# EXT-PHY.net
KiCad netlist of a schematic drawn in EAGLE
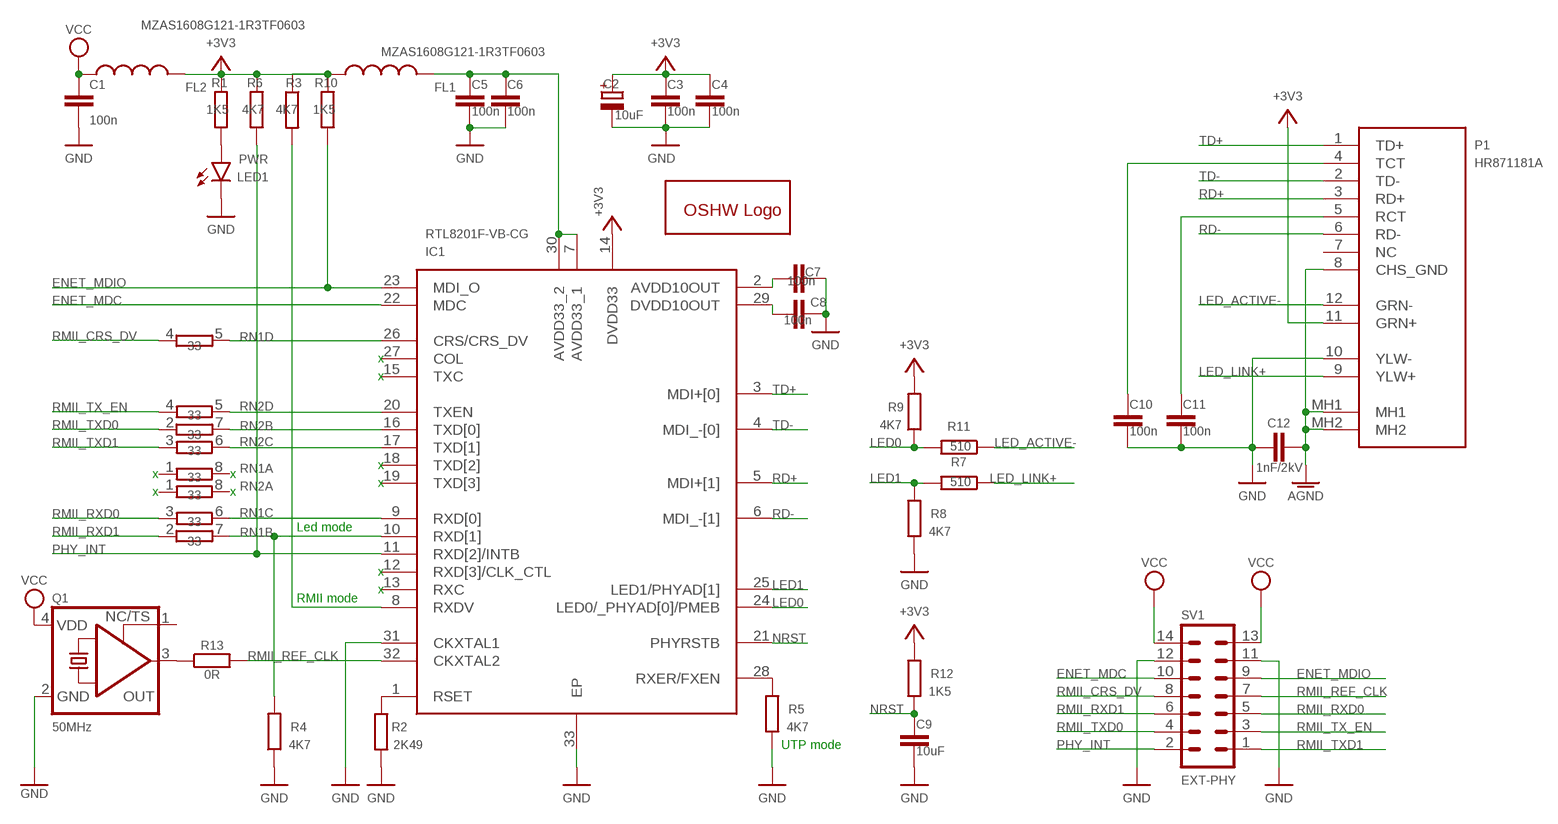
[diagram p0: schematic, sheet 1]

(export (version "E")
  (design (tool "Eeschema 10.0.6"))
  (components
    (comp (ref "C1")
      (value "100n")
      (footprint "eagle-import:C0603")
      (libsource (lib "eagle-import") (part "C-EUC0603"))
    )
    (comp (ref "C2")
      (value "10uF")
      (footprint "eagle-import:A_3216-18R")
      (libsource (lib "eagle-import") (part "CPOL-EUA/3216-18R"))
    )
    (comp (ref "C3")
      (value "100n")
      (footprint "eagle-import:C0603")
      (libsource (lib "eagle-import") (part "C-EUC0603"))
    )
    (comp (ref "C4")
      (value "100n")
      (footprint "eagle-import:C0603")
      (libsource (lib "eagle-import") (part "C-EUC0603"))
    )
    (comp (ref "C5")
      (value "100n")
      (footprint "eagle-import:C0603")
      (libsource (lib "eagle-import") (part "C-EUC0603"))
    )
    (comp (ref "C6")
      (value "100n")
      (footprint "eagle-import:C0603")
      (libsource (lib "eagle-import") (part "C-EUC0603"))
    )
    (comp (ref "C7")
      (value "100n")
      (footprint "eagle-import:C0603")
      (libsource (lib "eagle-import") (part "C-EUC0603"))
    )
    (comp (ref "C8")
      (value "100n")
      (footprint "eagle-import:C0603")
      (libsource (lib "eagle-import") (part "C-EUC0603"))
    )
    (comp (ref "C9")
      (value "10uF")
      (footprint "eagle-import:C0603")
      (libsource (lib "eagle-import") (part "C-EUC0603"))
    )
    (comp (ref "C10")
      (value "100n")
      (footprint "eagle-import:C0603")
      (libsource (lib "eagle-import") (part "C-EUC0603"))
    )
    (comp (ref "C11")
      (value "100n")
      (footprint "eagle-import:C0603")
      (libsource (lib "eagle-import") (part "C-EUC0603"))
    )
    (comp (ref "C12")
      (value "1nF/2kV")
      (footprint "eagle-import:C1206")
      (fields (field (name "SPICEPREFIX") "C"))
      (libsource (lib "eagle-import") (part "C-EUC1206"))
    )
    (comp (ref "FL1")
      (value "MZAS1608G121-1R3TF0603")
      (footprint "eagle-import:0603")
      (libsource (lib "eagle-import") (part "MZAS1608G121-1R3TF0603"))
    )
    (comp (ref "FL2")
      (value "MZAS1608G121-1R3TF0603")
      (footprint "eagle-import:0603")
      (libsource (lib "eagle-import") (part "MZAS1608G121-1R3TF0603"))
    )
    (comp (ref "GOLD_ORB_SM1")
      (value "OSHWLOGOLOGO5MM")
      (footprint "eagle-import:OSHW_5MM")
      (libsource (lib "eagle-import") (part "OSHWLOGOLOGO5MM"))
    )
    (comp (ref "IC1")
      (value "RTL8201F-VB-CG")
      (footprint "eagle-import:QFN50P500X500X100-33N")
      (libsource (lib "eagle-import") (part "RTL8201F-VB-CG"))
    )
    (comp (ref "LED1")
      (value "PWR")
      (footprint "eagle-import:CHIP-LED0603")
      (libsource (lib "eagle-import") (part "LEDCHIP-LED0603"))
    )
    (comp (ref "P1")
      (value "HR871181A")
      (footprint "eagle-import:HR871181A")
      (libsource (lib "eagle-import") (part "HR871181A"))
    )
    (comp (ref "Q1")
      (value "50MHz")
      (footprint "eagle-import:3.2X2.5_KXO-V96")
      (libsource (lib "eagle-import") (part "KXO-PXO/XO-V96"))
    )
    (comp (ref "R1")
      (value "1K5")
      (footprint "eagle-import:R0603")
      (libsource (lib "eagle-import") (part "R-EU_R0603"))
    )
    (comp (ref "R2")
      (value "2K49")
      (footprint "eagle-import:R0603")
      (libsource (lib "eagle-import") (part "R-EU_R0603"))
    )
    (comp (ref "R3")
      (value "4K7")
      (footprint "eagle-import:R0603")
      (libsource (lib "eagle-import") (part "R-EU_R0603"))
    )
    (comp (ref "R4")
      (value "4K7")
      (footprint "eagle-import:R0603")
      (libsource (lib "eagle-import") (part "R-EU_R0603"))
    )
    (comp (ref "R5")
      (value "4K7")
      (footprint "eagle-import:R0603")
      (libsource (lib "eagle-import") (part "R-EU_R0603"))
    )
    (comp (ref "R6")
      (value "4K7")
      (footprint "eagle-import:R0603")
      (libsource (lib "eagle-import") (part "R-EU_R0603"))
    )
    (comp (ref "R7")
      (value "510")
      (footprint "eagle-import:R0603")
      (libsource (lib "eagle-import") (part "R-EU_R0603"))
    )
    (comp (ref "R8")
      (value "4K7")
      (footprint "eagle-import:R0603")
      (libsource (lib "eagle-import") (part "R-EU_R0603"))
    )
    (comp (ref "R9")
      (value "4K7")
      (footprint "eagle-import:R0603")
      (libsource (lib "eagle-import") (part "R-EU_R0603"))
    )
    (comp (ref "R10")
      (value "1K5")
      (footprint "eagle-import:R0603")
      (libsource (lib "eagle-import") (part "R-EU_R0603"))
    )
    (comp (ref "R11")
      (value "510")
      (footprint "eagle-import:R0603")
      (libsource (lib "eagle-import") (part "R-EU_R0603"))
    )
    (comp (ref "R12")
      (value "1K5")
      (footprint "eagle-import:R0603")
      (libsource (lib "eagle-import") (part "R-EU_R0603"))
    )
    (comp (ref "R13")
      (value "0R")
      (footprint "eagle-import:R0603")
      (libsource (lib "eagle-import") (part "R-EU_R0603"))
    )
    (comp (ref "RN1")
      (value "33")
      (footprint "eagle-import:4X0402ARV341")
      (fields (field (name "JLCPCB") "C25501"))
      (libsource (lib "eagle-import") (part "4R-N0402ARV341"))
    )
    (comp (ref "RN2")
      (value "33")
      (footprint "eagle-import:4X0402ARV341")
      (fields (field (name "JLCPCB") "C25501"))
      (libsource (lib "eagle-import") (part "4R-N0402ARV341"))
    )
    (comp (ref "SV1")
      (value "EXT-PHY")
      (footprint "eagle-import:MA07-2W")
      (libsource (lib "eagle-import") (part "MA07-2W"))
    )
  )
  (nets
    (net (code "1") (name "+3V3") (class "Default")
      (node (ref "C2") (pin "+") (pinfunction "+_+") (pintype "passive"))
      (node (ref "C3") (pin "1") (pinfunction "1_1") (pintype "passive"))
      (node (ref "C4") (pin "1") (pinfunction "1_1") (pintype "passive"))
      (node (ref "FL1") (pin "1") (pinfunction "1_1") (pintype "passive"))
      (node (ref "FL2") (pin "2") (pinfunction "2_2") (pintype "passive"))
      (node (ref "IC1") (pin "14") (pinfunction "DVDD33_14") (pintype "bidirectional"))
      (node (ref "P1") (pin "11") (pinfunction "GRN+_11") (pintype "bidirectional"))
      (node (ref "R1") (pin "2") (pinfunction "2_2") (pintype "passive"))
      (node (ref "R10") (pin "2") (pinfunction "2_2") (pintype "passive"))
      (node (ref "R12") (pin "2") (pinfunction "2_2") (pintype "passive"))
      (node (ref "R3") (pin "1") (pinfunction "1_1") (pintype "passive"))
      (node (ref "R6") (pin "2") (pinfunction "2_2") (pintype "passive"))
      (node (ref "R9") (pin "2") (pinfunction "2_2") (pintype "passive"))
    )
    (net (code "2") (name "/ENET_MDC") (class "Default")
      (node (ref "IC1") (pin "22") (pinfunction "MDC_22") (pintype "bidirectional"))
      (node (ref "SV1") (pin "10") (pinfunction "10_10") (pintype "passive"))
    )
    (net (code "3") (name "/ENET_MDIO") (class "Default")
      (node (ref "IC1") (pin "23") (pinfunction "MDI_O_23") (pintype "bidirectional"))
      (node (ref "R10") (pin "1") (pinfunction "1_1") (pintype "passive"))
      (node (ref "SV1") (pin "9") (pinfunction "9_9") (pintype "passive"))
    )
    (net (code "4") (name "/LED0") (class "Default")
      (node (ref "IC1") (pin "24") (pinfunction "LED0/_PHYAD[0]/PMEB_24") (pintype "bidirectional"))
      (node (ref "R11") (pin "2") (pinfunction "2_2") (pintype "passive"))
      (node (ref "R9") (pin "1") (pinfunction "1_1") (pintype "passive"))
    )
    (net (code "5") (name "/LED1") (class "Default")
      (node (ref "IC1") (pin "25") (pinfunction "LED1/PHYAD[1]_25") (pintype "bidirectional"))
      (node (ref "R7") (pin "2") (pinfunction "2_2") (pintype "passive"))
      (node (ref "R8") (pin "2") (pinfunction "2_2") (pintype "passive"))
    )
    (net (code "6") (name "/LED_ACTIVE-") (class "Default")
      (node (ref "P1") (pin "12") (pinfunction "GRN-_12") (pintype "bidirectional"))
      (node (ref "R11") (pin "1") (pinfunction "1_1") (pintype "passive"))
    )
    (net (code "7") (name "/LED_LINK+") (class "Default")
      (node (ref "P1") (pin "9") (pinfunction "YLW+_9") (pintype "bidirectional"))
      (node (ref "R7") (pin "1") (pinfunction "1_1") (pintype "passive"))
    )
    (net (code "8") (name "/NRST") (class "Default")
      (node (ref "C9") (pin "1") (pinfunction "1_1") (pintype "passive"))
      (node (ref "IC1") (pin "21") (pinfunction "PHYRSTB_21") (pintype "bidirectional"))
      (node (ref "R12") (pin "1") (pinfunction "1_1") (pintype "passive"))
    )
    (net (code "9") (name "/PHY_INT") (class "Default")
      (node (ref "IC1") (pin "11") (pinfunction "RXD[2]/INTB_11") (pintype "bidirectional"))
      (node (ref "R6") (pin "1") (pinfunction "1_1") (pintype "passive"))
      (node (ref "SV1") (pin "2") (pinfunction "2_2") (pintype "passive"))
    )
    (net (code "10") (name "/RD+") (class "Default")
      (node (ref "IC1") (pin "5") (pinfunction "MDI+[1]_5") (pintype "bidirectional"))
      (node (ref "P1") (pin "3") (pinfunction "RD+_3") (pintype "bidirectional"))
    )
    (net (code "11") (name "/RD-") (class "Default")
      (node (ref "IC1") (pin "6") (pinfunction "MDI_-[1]_6") (pintype "bidirectional"))
      (node (ref "P1") (pin "6") (pinfunction "RD-_6") (pintype "bidirectional"))
    )
    (net (code "12") (name "/RMII_CRS_DV") (class "Default")
      (node (ref "RN1") (pin "4") (pinfunction "1_4") (pintype "passive"))
      (node (ref "SV1") (pin "8") (pinfunction "8_8") (pintype "passive"))
    )
    (net (code "13") (name "/RMII_REF_CLK") (class "Default")
      (node (ref "IC1") (pin "32") (pinfunction "CKXTAL2_32") (pintype "bidirectional"))
      (node (ref "R13") (pin "2") (pinfunction "2_2") (pintype "passive"))
      (node (ref "SV1") (pin "7") (pinfunction "7_7") (pintype "passive"))
    )
    (net (code "14") (name "/RMII_RXD0") (class "Default")
      (node (ref "RN1") (pin "3") (pinfunction "1_3") (pintype "passive"))
      (node (ref "SV1") (pin "5") (pinfunction "5_5") (pintype "passive"))
    )
    (net (code "15") (name "/RMII_RXD1") (class "Default")
      (node (ref "RN1") (pin "2") (pinfunction "1_2") (pintype "passive"))
      (node (ref "SV1") (pin "6") (pinfunction "6_6") (pintype "passive"))
    )
    (net (code "16") (name "/RMII_TXD0") (class "Default")
      (node (ref "RN2") (pin "2") (pinfunction "1_2") (pintype "passive"))
      (node (ref "SV1") (pin "4") (pinfunction "4_4") (pintype "passive"))
    )
    (net (code "17") (name "/RMII_TXD1") (class "Default")
      (node (ref "RN2") (pin "3") (pinfunction "1_3") (pintype "passive"))
      (node (ref "SV1") (pin "1") (pinfunction "1_1") (pintype "passive"))
    )
    (net (code "18") (name "/RMII_TX_EN") (class "Default")
      (node (ref "RN2") (pin "4") (pinfunction "1_4") (pintype "passive"))
      (node (ref "SV1") (pin "3") (pinfunction "3_3") (pintype "passive"))
    )
    (net (code "19") (name "/TD+") (class "Default")
      (node (ref "IC1") (pin "3") (pinfunction "MDI+[0]_3") (pintype "bidirectional"))
      (node (ref "P1") (pin "1") (pinfunction "TD+_1") (pintype "bidirectional"))
    )
    (net (code "20") (name "/TD-") (class "Default")
      (node (ref "IC1") (pin "4") (pinfunction "MDI_-[0]_4") (pintype "bidirectional"))
      (node (ref "P1") (pin "2") (pinfunction "TD-_2") (pintype "bidirectional"))
    )
    (net (code "21") (name "AGND") (class "Default")
      (node (ref "C12") (pin "2") (pinfunction "2_2") (pintype "passive"))
      (node (ref "P1") (pin "8") (pinfunction "CHS_GND_8") (pintype "bidirectional"))
      (node (ref "P1") (pin "MH1") (pinfunction "MH1_MH1") (pintype "bidirectional"))
      (node (ref "P1") (pin "MH2") (pinfunction "MH2_MH2") (pintype "bidirectional"))
    )
    (net (code "22") (name "GND") (class "Default")
      (node (ref "C1") (pin "2") (pinfunction "2_2") (pintype "passive"))
      (node (ref "C10") (pin "2") (pinfunction "2_2") (pintype "passive"))
      (node (ref "C11") (pin "2") (pinfunction "2_2") (pintype "passive"))
      (node (ref "C12") (pin "1") (pinfunction "1_1") (pintype "passive"))
      (node (ref "C2") (pin "-") (pinfunction "-_-") (pintype "passive"))
      (node (ref "C3") (pin "2") (pinfunction "2_2") (pintype "passive"))
      (node (ref "C4") (pin "2") (pinfunction "2_2") (pintype "passive"))
      (node (ref "C5") (pin "2") (pinfunction "2_2") (pintype "passive"))
      (node (ref "C6") (pin "2") (pinfunction "2_2") (pintype "passive"))
      (node (ref "C7") (pin "2") (pinfunction "2_2") (pintype "passive"))
      (node (ref "C8") (pin "1") (pinfunction "1_1") (pintype "passive"))
      (node (ref "C9") (pin "2") (pinfunction "2_2") (pintype "passive"))
      (node (ref "IC1") (pin "31") (pinfunction "CKXTAL1_31") (pintype "bidirectional"))
      (node (ref "IC1") (pin "33") (pinfunction "EP_33") (pintype "bidirectional"))
      (node (ref "LED1") (pin "C") (pinfunction "C_C") (pintype "passive"))
      (node (ref "P1") (pin "10") (pinfunction "YLW-_10") (pintype "bidirectional"))
      (node (ref "Q1") (pin "2") (pinfunction "GND_2") (pintype "power_in"))
      (node (ref "R2") (pin "2") (pinfunction "2_2") (pintype "passive"))
      (node (ref "R4") (pin "1") (pinfunction "1_1") (pintype "passive"))
      (node (ref "R5") (pin "1") (pinfunction "1_1") (pintype "passive"))
      (node (ref "R8") (pin "1") (pinfunction "1_1") (pintype "passive"))
      (node (ref "SV1") (pin "11") (pinfunction "11_11") (pintype "passive"))
      (node (ref "SV1") (pin "12") (pinfunction "12_12") (pintype "passive"))
    )
    (net (code "23") (name "Net-(IC1-AVDD10OUT)") (class "Default")
      (node (ref "C7") (pin "1") (pinfunction "1_1") (pintype "passive"))
      (node (ref "IC1") (pin "2") (pinfunction "AVDD10OUT_2") (pintype "bidirectional"))
    )
    (net (code "24") (name "Net-(IC1-AVDD33_1)") (class "Default")
      (node (ref "C5") (pin "1") (pinfunction "1_1") (pintype "passive"))
      (node (ref "C6") (pin "1") (pinfunction "1_1") (pintype "passive"))
      (node (ref "FL1") (pin "2") (pinfunction "2_2") (pintype "passive"))
      (node (ref "IC1") (pin "30") (pinfunction "AVDD33_2_30") (pintype "bidirectional"))
      (node (ref "IC1") (pin "7") (pinfunction "AVDD33_1_7") (pintype "bidirectional"))
    )
    (net (code "25") (name "Net-(IC1-CRS{slash}CRS_DV)") (class "Default")
      (node (ref "IC1") (pin "26") (pinfunction "CRS/CRS_DV_26") (pintype "bidirectional"))
      (node (ref "RN1") (pin "5") (pinfunction "2_5") (pintype "passive"))
    )
    (net (code "26") (name "Net-(IC1-DVDD10OUT)") (class "Default")
      (node (ref "C8") (pin "2") (pinfunction "2_2") (pintype "passive"))
      (node (ref "IC1") (pin "29") (pinfunction "DVDD10OUT_29") (pintype "bidirectional"))
    )
    (net (code "27") (name "Net-(IC1-RSET)") (class "Default")
      (node (ref "IC1") (pin "1") (pinfunction "RSET_1") (pintype "bidirectional"))
      (node (ref "R2") (pin "1") (pinfunction "1_1") (pintype "passive"))
    )
    (net (code "28") (name "Net-(IC1-RXDV)") (class "Default")
      (node (ref "IC1") (pin "8") (pinfunction "RXDV_8") (pintype "bidirectional"))
      (node (ref "R3") (pin "2") (pinfunction "2_2") (pintype "passive"))
    )
    (net (code "29") (name "Net-(IC1-RXD[0])") (class "Default")
      (node (ref "IC1") (pin "9") (pinfunction "RXD[0]_9") (pintype "bidirectional"))
      (node (ref "RN1") (pin "6") (pinfunction "2_6") (pintype "passive"))
    )
    (net (code "30") (name "Net-(IC1-RXD[1])") (class "Default")
      (node (ref "IC1") (pin "10") (pinfunction "RXD[1]_10") (pintype "bidirectional"))
      (node (ref "R4") (pin "2") (pinfunction "2_2") (pintype "passive"))
      (node (ref "RN1") (pin "7") (pinfunction "2_7") (pintype "passive"))
    )
    (net (code "31") (name "Net-(IC1-RXER{slash}FXEN)") (class "Default")
      (node (ref "IC1") (pin "28") (pinfunction "RXER/FXEN_28") (pintype "bidirectional"))
      (node (ref "R5") (pin "2") (pinfunction "2_2") (pintype "passive"))
    )
    (net (code "32") (name "Net-(IC1-TXD[0])") (class "Default")
      (node (ref "IC1") (pin "16") (pinfunction "TXD[0]_16") (pintype "bidirectional"))
      (node (ref "RN2") (pin "7") (pinfunction "2_7") (pintype "passive"))
    )
    (net (code "33") (name "Net-(IC1-TXD[1])") (class "Default")
      (node (ref "IC1") (pin "17") (pinfunction "TXD[1]_17") (pintype "bidirectional"))
      (node (ref "RN2") (pin "6") (pinfunction "2_6") (pintype "passive"))
    )
    (net (code "34") (name "Net-(IC1-TXEN)") (class "Default")
      (node (ref "IC1") (pin "20") (pinfunction "TXEN_20") (pintype "bidirectional"))
      (node (ref "RN2") (pin "5") (pinfunction "2_5") (pintype "passive"))
    )
    (net (code "35") (name "Net-(LED1-PadA)") (class "Default")
      (node (ref "LED1") (pin "A") (pinfunction "A_A") (pintype "passive"))
      (node (ref "R1") (pin "1") (pinfunction "1_1") (pintype "passive"))
    )
    (net (code "36") (name "Net-(P1-RCT)") (class "Default")
      (node (ref "C11") (pin "1") (pinfunction "1_1") (pintype "passive"))
      (node (ref "P1") (pin "5") (pinfunction "RCT_5") (pintype "bidirectional"))
    )
    (net (code "37") (name "Net-(P1-TCT)") (class "Default")
      (node (ref "C10") (pin "1") (pinfunction "1_1") (pintype "passive"))
      (node (ref "P1") (pin "4") (pinfunction "TCT_4") (pintype "bidirectional"))
    )
    (net (code "38") (name "Net-(Q1-OUT)") (class "Default")
      (node (ref "Q1") (pin "3") (pinfunction "OUT_3") (pintype "output"))
      (node (ref "R13") (pin "1") (pinfunction "1_1") (pintype "passive"))
    )
    (net (code "39") (name "VCC") (class "Default")
      (node (ref "C1") (pin "1") (pinfunction "1_1") (pintype "passive"))
      (node (ref "FL2") (pin "1") (pinfunction "1_1") (pintype "passive"))
      (node (ref "Q1") (pin "4") (pinfunction "VDD_4") (pintype "power_in"))
      (node (ref "SV1") (pin "13") (pinfunction "13_13") (pintype "passive"))
      (node (ref "SV1") (pin "14") (pinfunction "14_14") (pintype "passive"))
    )
    (net (code "40") (name "unconnected-(IC1-COL-Pad27)") (class "Default")
      (node (ref "IC1") (pin "27") (pinfunction "COL_27") (pintype "bidirectional"))
    )
    (net (code "41") (name "unconnected-(IC1-RXC-Pad13)") (class "Default")
      (node (ref "IC1") (pin "13") (pinfunction "RXC_13") (pintype "bidirectional"))
    )
    (net (code "42") (name "unconnected-(IC1-RXD[3]{slash}CLK_CTL-Pad12)") (class "Default")
      (node (ref "IC1") (pin "12") (pinfunction "RXD[3]/CLK_CTL_12") (pintype "bidirectional"))
    )
    (net (code "43") (name "unconnected-(IC1-TXC-Pad15)") (class "Default")
      (node (ref "IC1") (pin "15") (pinfunction "TXC_15") (pintype "bidirectional"))
    )
    (net (code "44") (name "unconnected-(IC1-TXD[2]-Pad18)") (class "Default")
      (node (ref "IC1") (pin "18") (pinfunction "TXD[2]_18") (pintype "bidirectional"))
    )
    (net (code "45") (name "unconnected-(IC1-TXD[3]-Pad19)") (class "Default")
      (node (ref "IC1") (pin "19") (pinfunction "TXD[3]_19") (pintype "bidirectional"))
    )
    (net (code "46") (name "unconnected-(P1-NC-Pad7)") (class "Default")
      (node (ref "P1") (pin "7") (pinfunction "NC_7") (pintype "bidirectional"))
    )
    (net (code "47") (name "unconnected-(Q1-TS-Pad1)") (class "Default")
      (node (ref "Q1") (pin "1") (pinfunction "TS_1") (pintype "passive"))
    )
    (net (code "48") (name "unconnected-(RN1-Pad1)") (class "Default")
      (node (ref "RN1") (pin "1") (pinfunction "1_1") (pintype "passive"))
    )
    (net (code "49") (name "unconnected-(RN1A-2-Pad8)") (class "Default")
      (node (ref "RN1") (pin "8") (pinfunction "2_8") (pintype "passive"))
    )
    (net (code "50") (name "unconnected-(RN2-Pad1)") (class "Default")
      (node (ref "RN2") (pin "1") (pinfunction "1_1") (pintype "passive"))
    )
    (net (code "51") (name "unconnected-(RN2A-2-Pad8)") (class "Default")
      (node (ref "RN2") (pin "8") (pinfunction "2_8") (pintype "passive"))
    )
  )
)
